# adc_spi_esp12E.net
KiCad netlist of a schematic drawn in EAGLE
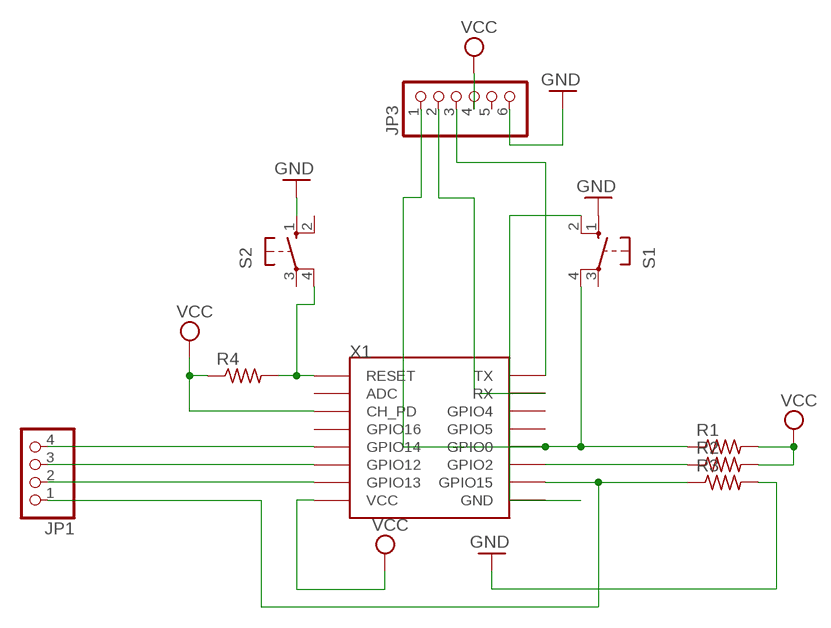
[diagram p0: schematic, sheet 1]

(export (version "E")
  (design (tool "Eeschema 10.0.6"))
  (components
    (comp (ref "JP1")
      (value "PINHD-1X4")
      (footprint "eagle-import:1X04")
      (libsource (lib "eagle-import") (part "PINHD-1X4"))
    )
    (comp (ref "JP3")
      (value "PINHD-1X6B")
      (footprint "eagle-import:1X06-BIG")
      (libsource (lib "eagle-import") (part "PINHD-1X6B"))
    )
    (comp (ref "R1")
      (value "R-US_0204/7")
      (footprint "eagle-import:0204_7")
      (libsource (lib "eagle-import") (part "R-US_0204/7"))
    )
    (comp (ref "R2")
      (value "R-US_0204/7")
      (footprint "eagle-import:0204_7")
      (libsource (lib "eagle-import") (part "R-US_0204/7"))
    )
    (comp (ref "R3")
      (value "R-US_0204/7")
      (footprint "eagle-import:0204_7")
      (libsource (lib "eagle-import") (part "R-US_0204/7"))
    )
    (comp (ref "R4")
      (value "R-US_0204/5")
      (footprint "eagle-import:0204_5")
      (libsource (lib "eagle-import") (part "R-US_0204/5"))
    )
    (comp (ref "S1")
      (value "10-XX")
      (footprint "eagle-import:B3F-10XX")
      (fields (field (name "MPN") "B3F-1000"))
      (libsource (lib "eagle-import") (part "10-XX"))
    )
    (comp (ref "S2")
      (value "10-XX")
      (footprint "eagle-import:B3F-10XX")
      (fields (field (name "MPN") "B3F-1000"))
      (libsource (lib "eagle-import") (part "10-XX"))
    )
    (comp (ref "X1")
      (value "ESP12SMD")
      (footprint "eagle-import:ESP12-SMD")
      (libsource (lib "eagle-import") (part "ESP12SMD"))
    )
  )
  (nets
    (net (code "1") (name "GND") (class "Default")
      (node (ref "JP3") (pin "6") (pinfunction "6_6") (pintype "passive"))
      (node (ref "R3") (pin "2") (pinfunction "2_2") (pintype "passive"))
      (node (ref "S1") (pin "1") (pinfunction "S_1") (pintype "passive"))
      (node (ref "S2") (pin "1") (pinfunction "S_1") (pintype "passive"))
    )
    (net (code "2") (name "Net-(JP1-Pad1)") (class "Default")
      (node (ref "JP1") (pin "1") (pinfunction "1_1") (pintype "passive"))
      (node (ref "R3") (pin "1") (pinfunction "1_1") (pintype "passive"))
      (node (ref "X1") (pin "GPIO15") (pinfunction "GPIO15_GPIO15") (pintype "bidirectional"))
    )
    (net (code "3") (name "Net-(JP1-Pad2)") (class "Default")
      (node (ref "JP1") (pin "2") (pinfunction "2_2") (pintype "passive"))
      (node (ref "X1") (pin "GPIO13") (pinfunction "GPIO13_GPIO13") (pintype "bidirectional"))
    )
    (net (code "4") (name "Net-(JP1-Pad3)") (class "Default")
      (node (ref "JP1") (pin "3") (pinfunction "3_3") (pintype "passive"))
      (node (ref "X1") (pin "GPIO12") (pinfunction "GPIO12_GPIO12") (pintype "bidirectional"))
    )
    (net (code "5") (name "Net-(JP1-Pad4)") (class "Default")
      (node (ref "JP1") (pin "4") (pinfunction "4_4") (pintype "passive"))
      (node (ref "X1") (pin "GPIO14") (pinfunction "GPIO14_GPIO14") (pintype "bidirectional"))
    )
    (net (code "6") (name "Net-(R2-Pad1)") (class "Default")
      (node (ref "R2") (pin "1") (pinfunction "1_1") (pintype "passive"))
      (node (ref "X1") (pin "GPIO2") (pinfunction "GPIO2_GPIO2") (pintype "bidirectional"))
    )
    (net (code "7") (name "Net-(S1-P1)") (class "Default")
      (node (ref "JP3") (pin "1") (pinfunction "1_1") (pintype "passive"))
      (node (ref "R1") (pin "1") (pinfunction "1_1") (pintype "passive"))
      (node (ref "S1") (pin "4") (pinfunction "P1_4") (pintype "passive"))
      (node (ref "X1") (pin "GPIO0") (pinfunction "GPIO0_GPIO0") (pintype "bidirectional"))
    )
    (net (code "8") (name "Net-(S1-S1)") (class "Default")
      (node (ref "S1") (pin "2") (pinfunction "S1_2") (pintype "passive"))
      (node (ref "X1") (pin "GND") (pinfunction "GND_GND") (pintype "bidirectional"))
    )
    (net (code "9") (name "Net-(S2-P1)") (class "Default")
      (node (ref "R4") (pin "2") (pinfunction "2_2") (pintype "passive"))
      (node (ref "S2") (pin "4") (pinfunction "P1_4") (pintype "passive"))
      (node (ref "X1") (pin "RESET") (pinfunction "RESET_RESET") (pintype "bidirectional"))
    )
    (net (code "10") (name "Net-(X1-RX)") (class "Default")
      (node (ref "JP3") (pin "2") (pinfunction "2_2") (pintype "passive"))
      (node (ref "X1") (pin "RXD0") (pinfunction "RX_RXD0") (pintype "bidirectional"))
    )
    (net (code "11") (name "Net-(X1-TX)") (class "Default")
      (node (ref "JP3") (pin "3") (pinfunction "3_3") (pintype "passive"))
      (node (ref "X1") (pin "TXD0") (pinfunction "TX_TXD0") (pintype "bidirectional"))
    )
    (net (code "12") (name "VCC") (class "Default")
      (node (ref "JP3") (pin "4") (pinfunction "4_4") (pintype "passive"))
      (node (ref "R1") (pin "2") (pinfunction "2_2") (pintype "passive"))
      (node (ref "R2") (pin "2") (pinfunction "2_2") (pintype "passive"))
      (node (ref "R4") (pin "1") (pinfunction "1_1") (pintype "passive"))
      (node (ref "X1") (pin "CH_PD") (pinfunction "CH_PD_CH_PD") (pintype "bidirectional"))
      (node (ref "X1") (pin "VCC") (pinfunction "VCC_VCC") (pintype "bidirectional"))
    )
    (net (code "13") (name "unconnected-(JP3-Pad5)") (class "Default")
      (node (ref "JP3") (pin "5") (pinfunction "5_5") (pintype "passive"))
    )
    (net (code "14") (name "unconnected-(S1-P-Pad3)") (class "Default")
      (node (ref "S1") (pin "3") (pinfunction "P_3") (pintype "passive"))
    )
    (net (code "15") (name "unconnected-(S2-P-Pad3)") (class "Default")
      (node (ref "S2") (pin "3") (pinfunction "P_3") (pintype "passive"))
    )
    (net (code "16") (name "unconnected-(S2-S1-Pad2)") (class "Default")
      (node (ref "S2") (pin "2") (pinfunction "S1_2") (pintype "passive"))
    )
    (net (code "17") (name "unconnected-(X1-PadADC)") (class "Default")
      (node (ref "X1") (pin "ADC") (pinfunction "ADC_ADC") (pintype "bidirectional"))
    )
    (net (code "18") (name "unconnected-(X1-PadGPIO4)") (class "Default")
      (node (ref "X1") (pin "GPIO4") (pinfunction "GPIO4_GPIO4") (pintype "bidirectional"))
    )
    (net (code "19") (name "unconnected-(X1-PadGPIO5)") (class "Default")
      (node (ref "X1") (pin "GPIO5") (pinfunction "GPIO5_GPIO5") (pintype "bidirectional"))
    )
    (net (code "20") (name "unconnected-(X1-PadGPIO16)") (class "Default")
      (node (ref "X1") (pin "GPIO16") (pinfunction "GPIO16_GPIO16") (pintype "bidirectional"))
    )
  )
)
